# LED_BAR.net
KiCad netlist of a schematic drawn in EAGLE
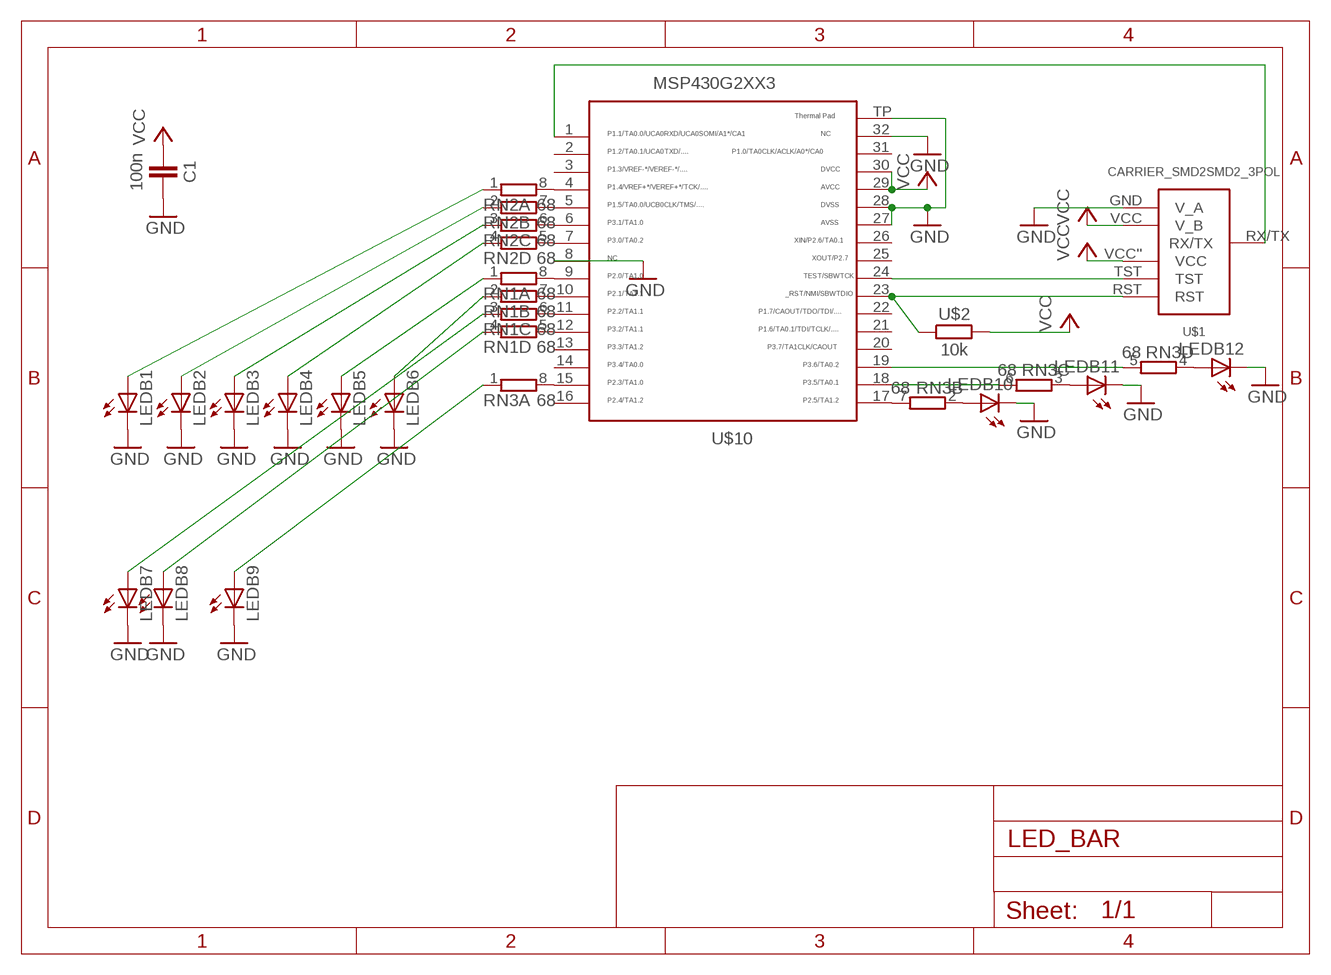
[diagram p0: schematic, sheet 1]

(export (version "E")
  (design (tool "Eeschema 10.0.6"))
  (components
    (comp (ref "C1")
      (value "100n")
      (footprint "eagle-import:603")
      (libsource (lib "eagle-import") (part "CAPACITOR"))
    )
    (comp (ref "LEDB1")
      (value "LEDCHIPLED_0603")
      (footprint "eagle-import:CHIPLED_0603")
      (libsource (lib "eagle-import") (part "LEDCHIPLED_0603"))
    )
    (comp (ref "LEDB2")
      (value "LEDCHIPLED_0603")
      (footprint "eagle-import:CHIPLED_0603")
      (libsource (lib "eagle-import") (part "LEDCHIPLED_0603"))
    )
    (comp (ref "LEDB3")
      (value "LEDCHIPLED_0603")
      (footprint "eagle-import:CHIPLED_0603")
      (libsource (lib "eagle-import") (part "LEDCHIPLED_0603"))
    )
    (comp (ref "LEDB4")
      (value "LEDCHIPLED_0603")
      (footprint "eagle-import:CHIPLED_0603")
      (libsource (lib "eagle-import") (part "LEDCHIPLED_0603"))
    )
    (comp (ref "LEDB5")
      (value "LEDCHIPLED_0603")
      (footprint "eagle-import:CHIPLED_0603")
      (libsource (lib "eagle-import") (part "LEDCHIPLED_0603"))
    )
    (comp (ref "LEDB6")
      (value "LEDCHIPLED_0603")
      (footprint "eagle-import:CHIPLED_0603")
      (libsource (lib "eagle-import") (part "LEDCHIPLED_0603"))
    )
    (comp (ref "LEDB7")
      (value "LEDCHIPLED_0603")
      (footprint "eagle-import:CHIPLED_0603")
      (libsource (lib "eagle-import") (part "LEDCHIPLED_0603"))
    )
    (comp (ref "LEDB8")
      (value "LEDCHIPLED_0603")
      (footprint "eagle-import:CHIPLED_0603")
      (libsource (lib "eagle-import") (part "LEDCHIPLED_0603"))
    )
    (comp (ref "LEDB9")
      (value "LEDCHIPLED_0603")
      (footprint "eagle-import:CHIPLED_0603")
      (libsource (lib "eagle-import") (part "LEDCHIPLED_0603"))
    )
    (comp (ref "LEDB10")
      (value "LEDCHIPLED_0603")
      (footprint "eagle-import:CHIPLED_0603")
      (libsource (lib "eagle-import") (part "LEDCHIPLED_0603"))
    )
    (comp (ref "LEDB11")
      (value "LEDCHIPLED_0603")
      (footprint "eagle-import:CHIPLED_0603")
      (libsource (lib "eagle-import") (part "LEDCHIPLED_0603"))
    )
    (comp (ref "LEDB12")
      (value "LEDCHIPLED_0603")
      (footprint "eagle-import:CHIPLED_0603")
      (libsource (lib "eagle-import") (part "LEDCHIPLED_0603"))
    )
    (comp (ref "RN1")
      (value "68")
      (footprint "eagle-import:0603-ARC")
      (libsource (lib "eagle-import") (part "4R-N0603-ARC"))
    )
    (comp (ref "RN2")
      (value "68")
      (footprint "eagle-import:0603-ARC")
      (libsource (lib "eagle-import") (part "4R-N0603-ARC"))
    )
    (comp (ref "RN3")
      (value "68")
      (footprint "eagle-import:0603-ARC")
      (libsource (lib "eagle-import") (part "4R-N0603-ARC"))
    )
    (comp (ref "U$1")
      (value "CARRIER_SMD2SMD2_3POL")
      (footprint "eagle-import:CARRIER_SMD2_3POL")
      (libsource (lib "eagle-import") (part "CARRIER_SMD2SMD2_3POL"))
    )
    (comp (ref "U$2")
      (value "10k")
      (footprint "eagle-import:603")
      (libsource (lib "eagle-import") (part "RESISTOR0603"))
    )
    (comp (ref "U$10")
      (value "MSP430G2553")
      (footprint "eagle-import:QFN32")
      (libsource (lib "eagle-import") (part "MSP430G2553"))
    )
  )
  (nets
    (net (code "1") (name "GND") (class "Default")
      (node (ref "C1") (pin "2") (pinfunction "2_2") (pintype "passive"))
      (node (ref "LEDB1") (pin "C") (pinfunction "C_C") (pintype "passive"))
      (node (ref "LEDB10") (pin "C") (pinfunction "C_C") (pintype "passive"))
      (node (ref "LEDB11") (pin "C") (pinfunction "C_C") (pintype "passive"))
      (node (ref "LEDB12") (pin "C") (pinfunction "C_C") (pintype "passive"))
      (node (ref "LEDB2") (pin "C") (pinfunction "C_C") (pintype "passive"))
      (node (ref "LEDB3") (pin "C") (pinfunction "C_C") (pintype "passive"))
      (node (ref "LEDB4") (pin "C") (pinfunction "C_C") (pintype "passive"))
      (node (ref "LEDB5") (pin "C") (pinfunction "C_C") (pintype "passive"))
      (node (ref "LEDB6") (pin "C") (pinfunction "C_C") (pintype "passive"))
      (node (ref "LEDB7") (pin "C") (pinfunction "C_C") (pintype "passive"))
      (node (ref "LEDB8") (pin "C") (pinfunction "C_C") (pintype "passive"))
      (node (ref "LEDB9") (pin "C") (pinfunction "C_C") (pintype "passive"))
      (node (ref "U$1") (pin "GND") (pinfunction "V_A_GND") (pintype "bidirectional"))
      (node (ref "U$10") (pin "27") (pinfunction "27_27") (pintype "bidirectional"))
      (node (ref "U$10") (pin "28") (pinfunction "28_28") (pintype "bidirectional"))
      (node (ref "U$10") (pin "32") (pinfunction "32_32") (pintype "bidirectional"))
      (node (ref "U$10") (pin "8") (pinfunction "8_8") (pintype "bidirectional"))
      (node (ref "U$10") (pin "TP") (pinfunction "TP_TP") (pintype "bidirectional"))
    )
    (net (code "2") (name "Net-(LEDB1-PadA)") (class "Default")
      (node (ref "LEDB1") (pin "A") (pinfunction "A_A") (pintype "passive"))
      (node (ref "RN2") (pin "1") (pinfunction "1_1") (pintype "passive"))
    )
    (net (code "3") (name "Net-(LEDB5-PadA)") (class "Default")
      (node (ref "LEDB5") (pin "A") (pinfunction "A_A") (pintype "passive"))
      (node (ref "RN1") (pin "1") (pinfunction "1_1") (pintype "passive"))
    )
    (net (code "4") (name "Net-(LEDB9-PadA)") (class "Default")
      (node (ref "LEDB9") (pin "A") (pinfunction "A_A") (pintype "passive"))
      (node (ref "RN3") (pin "1") (pinfunction "1_1") (pintype "passive"))
    )
    (net (code "5") (name "Net-(RN1A-2)") (class "Default")
      (node (ref "RN1") (pin "8") (pinfunction "2_8") (pintype "passive"))
      (node (ref "U$10") (pin "9") (pinfunction "9_9") (pintype "bidirectional"))
    )
    (net (code "6") (name "Net-(RN1B-1)") (class "Default")
      (node (ref "LEDB6") (pin "A") (pinfunction "A_A") (pintype "passive"))
      (node (ref "RN1") (pin "2") (pinfunction "1_2") (pintype "passive"))
    )
    (net (code "7") (name "Net-(RN1B-2)") (class "Default")
      (node (ref "RN1") (pin "7") (pinfunction "2_7") (pintype "passive"))
      (node (ref "U$10") (pin "10") (pinfunction "10_10") (pintype "bidirectional"))
    )
    (net (code "8") (name "Net-(RN1C-1)") (class "Default")
      (node (ref "LEDB7") (pin "A") (pinfunction "A_A") (pintype "passive"))
      (node (ref "RN1") (pin "3") (pinfunction "1_3") (pintype "passive"))
    )
    (net (code "9") (name "Net-(RN1C-2)") (class "Default")
      (node (ref "RN1") (pin "6") (pinfunction "2_6") (pintype "passive"))
      (node (ref "U$10") (pin "11") (pinfunction "11_11") (pintype "bidirectional"))
    )
    (net (code "10") (name "Net-(RN1D-1)") (class "Default")
      (node (ref "LEDB8") (pin "A") (pinfunction "A_A") (pintype "passive"))
      (node (ref "RN1") (pin "4") (pinfunction "1_4") (pintype "passive"))
    )
    (net (code "11") (name "Net-(RN1D-2)") (class "Default")
      (node (ref "RN1") (pin "5") (pinfunction "2_5") (pintype "passive"))
      (node (ref "U$10") (pin "12") (pinfunction "12_12") (pintype "bidirectional"))
    )
    (net (code "12") (name "Net-(RN2A-2)") (class "Default")
      (node (ref "RN2") (pin "8") (pinfunction "2_8") (pintype "passive"))
      (node (ref "U$10") (pin "4") (pinfunction "4_4") (pintype "bidirectional"))
    )
    (net (code "13") (name "Net-(RN2B-1)") (class "Default")
      (node (ref "LEDB2") (pin "A") (pinfunction "A_A") (pintype "passive"))
      (node (ref "RN2") (pin "2") (pinfunction "1_2") (pintype "passive"))
    )
    (net (code "14") (name "Net-(RN2B-2)") (class "Default")
      (node (ref "RN2") (pin "7") (pinfunction "2_7") (pintype "passive"))
      (node (ref "U$10") (pin "5") (pinfunction "5_5") (pintype "bidirectional"))
    )
    (net (code "15") (name "Net-(RN2C-1)") (class "Default")
      (node (ref "LEDB3") (pin "A") (pinfunction "A_A") (pintype "passive"))
      (node (ref "RN2") (pin "3") (pinfunction "1_3") (pintype "passive"))
    )
    (net (code "16") (name "Net-(RN2C-2)") (class "Default")
      (node (ref "RN2") (pin "6") (pinfunction "2_6") (pintype "passive"))
      (node (ref "U$10") (pin "6") (pinfunction "6_6") (pintype "bidirectional"))
    )
    (net (code "17") (name "Net-(RN2D-1)") (class "Default")
      (node (ref "LEDB4") (pin "A") (pinfunction "A_A") (pintype "passive"))
      (node (ref "RN2") (pin "4") (pinfunction "1_4") (pintype "passive"))
    )
    (net (code "18") (name "Net-(RN2D-2)") (class "Default")
      (node (ref "RN2") (pin "5") (pinfunction "2_5") (pintype "passive"))
      (node (ref "U$10") (pin "7") (pinfunction "7_7") (pintype "bidirectional"))
    )
    (net (code "19") (name "Net-(RN3A-2)") (class "Default")
      (node (ref "RN3") (pin "8") (pinfunction "2_8") (pintype "passive"))
      (node (ref "U$10") (pin "15") (pinfunction "15_15") (pintype "bidirectional"))
    )
    (net (code "20") (name "Net-(RN3B-1)") (class "Default")
      (node (ref "LEDB10") (pin "A") (pinfunction "A_A") (pintype "passive"))
      (node (ref "RN3") (pin "2") (pinfunction "1_2") (pintype "passive"))
    )
    (net (code "21") (name "Net-(RN3B-2)") (class "Default")
      (node (ref "RN3") (pin "7") (pinfunction "2_7") (pintype "passive"))
      (node (ref "U$10") (pin "17") (pinfunction "17_17") (pintype "bidirectional"))
    )
    (net (code "22") (name "Net-(RN3C-1)") (class "Default")
      (node (ref "LEDB11") (pin "A") (pinfunction "A_A") (pintype "passive"))
      (node (ref "RN3") (pin "3") (pinfunction "1_3") (pintype "passive"))
    )
    (net (code "23") (name "Net-(RN3C-2)") (class "Default")
      (node (ref "RN3") (pin "6") (pinfunction "2_6") (pintype "passive"))
      (node (ref "U$10") (pin "18") (pinfunction "18_18") (pintype "bidirectional"))
    )
    (net (code "24") (name "Net-(RN3D-1)") (class "Default")
      (node (ref "LEDB12") (pin "A") (pinfunction "A_A") (pintype "passive"))
      (node (ref "RN3") (pin "4") (pinfunction "1_4") (pintype "passive"))
    )
    (net (code "25") (name "Net-(RN3D-2)") (class "Default")
      (node (ref "RN3") (pin "5") (pinfunction "2_5") (pintype "passive"))
      (node (ref "U$10") (pin "19") (pinfunction "19_19") (pintype "bidirectional"))
    )
    (net (code "26") (name "Net-(U$1-PadRST)") (class "Default")
      (node (ref "U$1") (pin "RST") (pinfunction "RST_RST") (pintype "bidirectional"))
      (node (ref "U$10") (pin "23") (pinfunction "23_23") (pintype "bidirectional"))
      (node (ref "U$2") (pin "1") (pinfunction "1_1") (pintype "passive"))
    )
    (net (code "27") (name "Net-(U$1-PadRX{slash}TX)") (class "Default")
      (node (ref "U$1") (pin "RX/TX") (pinfunction "RX/TX_RX/TX") (pintype "bidirectional"))
      (node (ref "U$10") (pin "1") (pinfunction "1_1") (pintype "bidirectional"))
    )
    (net (code "28") (name "Net-(U$1-PadTST)") (class "Default")
      (node (ref "U$1") (pin "TST") (pinfunction "TST_TST") (pintype "bidirectional"))
      (node (ref "U$10") (pin "24") (pinfunction "24_24") (pintype "bidirectional"))
    )
    (net (code "29") (name "VCC") (class "Default")
      (node (ref "C1") (pin "1") (pinfunction "1_1") (pintype "passive"))
      (node (ref "U$1") (pin "VCC") (pinfunction "V_B_VCC") (pintype "bidirectional"))
      (node (ref "U$1") (pin "VCC''") (pinfunction "VCC_VCC''") (pintype "bidirectional"))
      (node (ref "U$10") (pin "29") (pinfunction "29_29") (pintype "bidirectional"))
      (node (ref "U$10") (pin "30") (pinfunction "30_30") (pintype "bidirectional"))
      (node (ref "U$2") (pin "2") (pinfunction "2_2") (pintype "passive"))
    )
    (net (code "30") (name "unconnected-(U$10-Pad2)") (class "Default")
      (node (ref "U$10") (pin "2") (pinfunction "2_2") (pintype "bidirectional"))
    )
    (net (code "31") (name "unconnected-(U$10-Pad3)") (class "Default")
      (node (ref "U$10") (pin "3") (pinfunction "3_3") (pintype "bidirectional"))
    )
    (net (code "32") (name "unconnected-(U$10-Pad13)") (class "Default")
      (node (ref "U$10") (pin "13") (pinfunction "13_13") (pintype "bidirectional"))
    )
    (net (code "33") (name "unconnected-(U$10-Pad14)") (class "Default")
      (node (ref "U$10") (pin "14") (pinfunction "14_14") (pintype "bidirectional"))
    )
    (net (code "34") (name "unconnected-(U$10-Pad16)") (class "Default")
      (node (ref "U$10") (pin "16") (pinfunction "16_16") (pintype "bidirectional"))
    )
    (net (code "35") (name "unconnected-(U$10-Pad20)") (class "Default")
      (node (ref "U$10") (pin "20") (pinfunction "20_20") (pintype "bidirectional"))
    )
    (net (code "36") (name "unconnected-(U$10-Pad21)") (class "Default")
      (node (ref "U$10") (pin "21") (pinfunction "21_21") (pintype "bidirectional"))
    )
    (net (code "37") (name "unconnected-(U$10-Pad22)") (class "Default")
      (node (ref "U$10") (pin "22") (pinfunction "22_22") (pintype "bidirectional"))
    )
    (net (code "38") (name "unconnected-(U$10-Pad25)") (class "Default")
      (node (ref "U$10") (pin "25") (pinfunction "25_25") (pintype "bidirectional"))
    )
    (net (code "39") (name "unconnected-(U$10-Pad26)") (class "Default")
      (node (ref "U$10") (pin "26") (pinfunction "26_26") (pintype "bidirectional"))
    )
    (net (code "40") (name "unconnected-(U$10-Pad31)") (class "Default")
      (node (ref "U$10") (pin "31") (pinfunction "31_31") (pintype "bidirectional"))
    )
  )
)
